# lihini_pcb_2021-05-16.net
KiCad netlist of a schematic drawn in EasyEDA
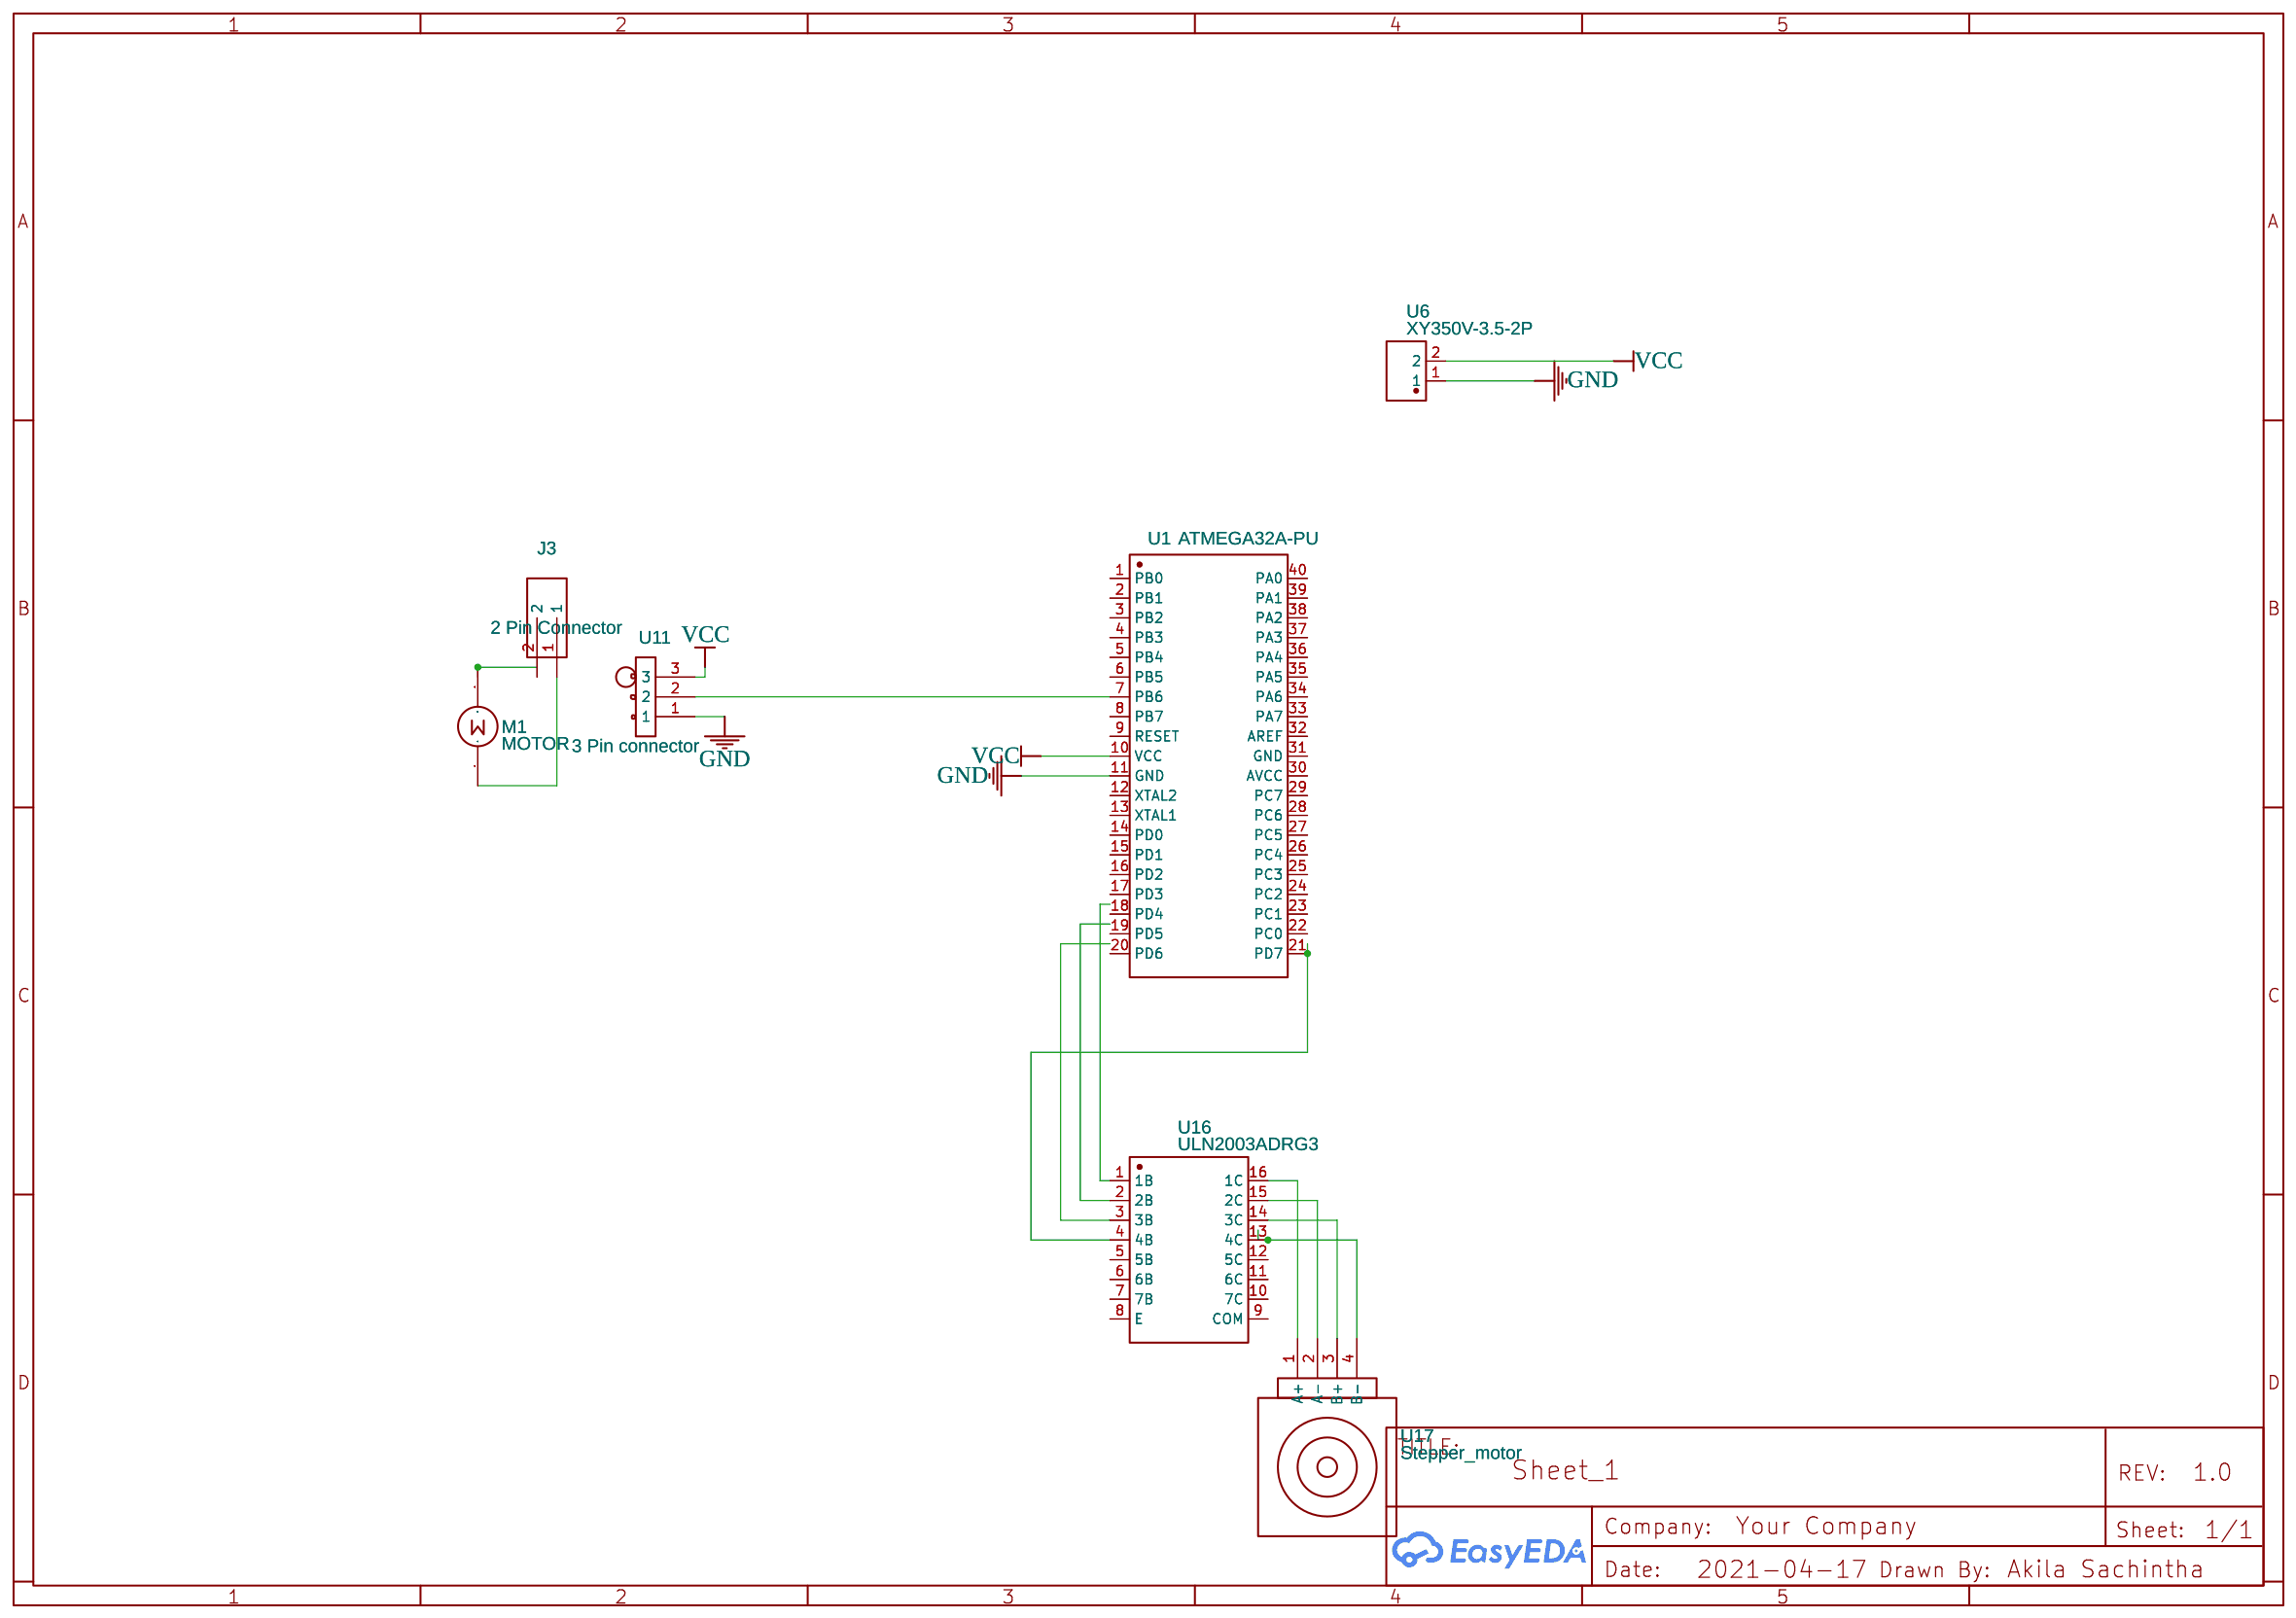
[diagram p0: schematic sheet]

(export (version "E")
  (design (tool "Eeschema 10.0.6"))
  (components
    (comp (ref "J3") (value "2 Pin Connector") (libsource (lib "") (part "2 Pin Connector")))
    (comp (ref "M1") (value "MOTOR") (libsource (lib "") (part "MOTOR")))
    (comp (ref "U1")
      (value "ATMEGA32A-PU")
      (fields (field (name "BOM_Supplier Part") "C12703"))
      (libsource (lib "") (part "ATMEGA32A-PU"))
    )
    (comp (ref "U6")
      (value "XY350V-3.5-2P")
      (fields (field (name "BOM_Supplier Part") "C784942"))
      (libsource (lib "") (part "XY350V-3.5-2P"))
    )
    (comp (ref "U11")
      (value "3 Pin connector")
      (fields (field (name "BOM_Manufacturer Part") "pin 3"))
      (libsource (lib "") (part "3 Pin connector"))
    )
    (comp (ref "U16") (value "ULN2003ADRG3") (libsource (lib "") (part "ULN2003ADRG3")))
    (comp (ref "U17")
      (value "Stepper_motor")
      (fields (field (name "BOM_Manufacturer Part") "NEMA 23 Stepper Motor"))
      (libsource (lib "") (part "Stepper_motor"))
    )
  )
  (nets
    (net (code "1") (name "GND") (class "Default")
      (node (ref "U1") (pin "11") (pinfunction "GND_11") (pintype "unspecified"))
      (node (ref "U11") (pin "1") (pinfunction "1_1") (pintype "unspecified"))
      (node (ref "U6") (pin "1") (pinfunction "1_1") (pintype "unspecified"))
    )
    (net (code "2") (name "Net-(J3-Pad1)") (class "Default")
      (node (ref "J3") (pin "1") (pinfunction "1_1") (pintype "unspecified"))
      (node (ref "M1") (pin "1") (pinfunction "1_1") (pintype "unspecified"))
    )
    (net (code "3") (name "Net-(U1-PB6)") (class "Default")
      (node (ref "U1") (pin "7") (pinfunction "PB6_7") (pintype "unspecified"))
      (node (ref "U11") (pin "2") (pinfunction "2_2") (pintype "unspecified"))
    )
    (net (code "4") (name "Net-(U1-PD7)") (class "Default")
      (node (ref "U1") (pin "21") (pinfunction "PD7_21") (pintype "unspecified"))
      (node (ref "U16") (pin "4") (pinfunction "4B_4") (pintype "unspecified"))
    )
    (net (code "5") (name "Net-(U16-1C)") (class "Default")
      (node (ref "U16") (pin "16") (pinfunction "1C_16") (pintype "unspecified"))
      (node (ref "U17") (pin "1") (pinfunction "A+_1") (pintype "unspecified"))
    )
    (net (code "6") (name "Net-(U16-2C)") (class "Default")
      (node (ref "U16") (pin "15") (pinfunction "2C_15") (pintype "unspecified"))
      (node (ref "U17") (pin "2") (pinfunction "A-_2") (pintype "unspecified"))
    )
    (net (code "7") (name "Net-(U16-3C)") (class "Default")
      (node (ref "U16") (pin "14") (pinfunction "3C_14") (pintype "unspecified"))
      (node (ref "U17") (pin "3") (pinfunction "B+_3") (pintype "unspecified"))
    )
    (net (code "8") (name "Net-(U16-4C)") (class "Default")
      (node (ref "U16") (pin "13") (pinfunction "4C_13") (pintype "unspecified"))
      (node (ref "U17") (pin "4") (pinfunction "B-_4") (pintype "unspecified"))
    )
    (net (code "9") (name "VCC") (class "Default")
      (node (ref "U1") (pin "10") (pinfunction "VCC_10") (pintype "unspecified"))
      (node (ref "U11") (pin "3") (pinfunction "3_3") (pintype "unspecified"))
      (node (ref "U6") (pin "2") (pinfunction "2_2") (pintype "unspecified"))
    )
    (net (code "10") (name "unconnected-(J3-Pad2)") (class "Default")
      (node (ref "J3") (pin "2") (pinfunction "2_2") (pintype "unspecified"))
    )
    (net (code "11") (name "unconnected-(M1-Pad2)") (class "Default")
      (node (ref "M1") (pin "2") (pinfunction "2_2") (pintype "unspecified"))
    )
    (net (code "12") (name "unconnected-(U1-AREF-Pad32)") (class "Default")
      (node (ref "U1") (pin "32") (pinfunction "AREF_32") (pintype "unspecified"))
    )
    (net (code "13") (name "unconnected-(U1-AVCC-Pad30)") (class "Default")
      (node (ref "U1") (pin "30") (pinfunction "AVCC_30") (pintype "unspecified"))
    )
    (net (code "14") (name "unconnected-(U1-GND-Pad31)") (class "Default")
      (node (ref "U1") (pin "31") (pinfunction "GND_31") (pintype "unspecified"))
    )
    (net (code "15") (name "unconnected-(U1-PA0-Pad40)") (class "Default")
      (node (ref "U1") (pin "40") (pinfunction "PA0_40") (pintype "unspecified"))
    )
    (net (code "16") (name "unconnected-(U1-PA1-Pad39)") (class "Default")
      (node (ref "U1") (pin "39") (pinfunction "PA1_39") (pintype "unspecified"))
    )
    (net (code "17") (name "unconnected-(U1-PA2-Pad38)") (class "Default")
      (node (ref "U1") (pin "38") (pinfunction "PA2_38") (pintype "unspecified"))
    )
    (net (code "18") (name "unconnected-(U1-PA3-Pad37)") (class "Default")
      (node (ref "U1") (pin "37") (pinfunction "PA3_37") (pintype "unspecified"))
    )
    (net (code "19") (name "unconnected-(U1-PA4-Pad36)") (class "Default")
      (node (ref "U1") (pin "36") (pinfunction "PA4_36") (pintype "unspecified"))
    )
    (net (code "20") (name "unconnected-(U1-PA5-Pad35)") (class "Default")
      (node (ref "U1") (pin "35") (pinfunction "PA5_35") (pintype "unspecified"))
    )
    (net (code "21") (name "unconnected-(U1-PA6-Pad34)") (class "Default")
      (node (ref "U1") (pin "34") (pinfunction "PA6_34") (pintype "unspecified"))
    )
    (net (code "22") (name "unconnected-(U1-PA7-Pad33)") (class "Default")
      (node (ref "U1") (pin "33") (pinfunction "PA7_33") (pintype "unspecified"))
    )
    (net (code "23") (name "unconnected-(U1-PB0-Pad1)") (class "Default")
      (node (ref "U1") (pin "1") (pinfunction "PB0_1") (pintype "unspecified"))
    )
    (net (code "24") (name "unconnected-(U1-PB1-Pad2)") (class "Default")
      (node (ref "U1") (pin "2") (pinfunction "PB1_2") (pintype "unspecified"))
    )
    (net (code "25") (name "unconnected-(U1-PB2-Pad3)") (class "Default")
      (node (ref "U1") (pin "3") (pinfunction "PB2_3") (pintype "unspecified"))
    )
    (net (code "26") (name "unconnected-(U1-PB3-Pad4)") (class "Default")
      (node (ref "U1") (pin "4") (pinfunction "PB3_4") (pintype "unspecified"))
    )
    (net (code "27") (name "unconnected-(U1-PB4-Pad5)") (class "Default")
      (node (ref "U1") (pin "5") (pinfunction "PB4_5") (pintype "unspecified"))
    )
    (net (code "28") (name "unconnected-(U1-PB5-Pad6)") (class "Default")
      (node (ref "U1") (pin "6") (pinfunction "PB5_6") (pintype "unspecified"))
    )
    (net (code "29") (name "unconnected-(U1-PB7-Pad8)") (class "Default")
      (node (ref "U1") (pin "8") (pinfunction "PB7_8") (pintype "unspecified"))
    )
    (net (code "30") (name "unconnected-(U1-PC0-Pad22)") (class "Default")
      (node (ref "U1") (pin "22") (pinfunction "PC0_22") (pintype "unspecified"))
    )
    (net (code "31") (name "unconnected-(U1-PC1-Pad23)") (class "Default")
      (node (ref "U1") (pin "23") (pinfunction "PC1_23") (pintype "unspecified"))
    )
    (net (code "32") (name "unconnected-(U1-PC2-Pad24)") (class "Default")
      (node (ref "U1") (pin "24") (pinfunction "PC2_24") (pintype "unspecified"))
    )
    (net (code "33") (name "unconnected-(U1-PC3-Pad25)") (class "Default")
      (node (ref "U1") (pin "25") (pinfunction "PC3_25") (pintype "unspecified"))
    )
    (net (code "34") (name "unconnected-(U1-PC4-Pad26)") (class "Default")
      (node (ref "U1") (pin "26") (pinfunction "PC4_26") (pintype "unspecified"))
    )
    (net (code "35") (name "unconnected-(U1-PC5-Pad27)") (class "Default")
      (node (ref "U1") (pin "27") (pinfunction "PC5_27") (pintype "unspecified"))
    )
    (net (code "36") (name "unconnected-(U1-PC6-Pad28)") (class "Default")
      (node (ref "U1") (pin "28") (pinfunction "PC6_28") (pintype "unspecified"))
    )
    (net (code "37") (name "unconnected-(U1-PC7-Pad29)") (class "Default")
      (node (ref "U1") (pin "29") (pinfunction "PC7_29") (pintype "unspecified"))
    )
    (net (code "38") (name "unconnected-(U1-PD0-Pad14)") (class "Default")
      (node (ref "U1") (pin "14") (pinfunction "PD0_14") (pintype "unspecified"))
    )
    (net (code "39") (name "unconnected-(U1-PD1-Pad15)") (class "Default")
      (node (ref "U1") (pin "15") (pinfunction "PD1_15") (pintype "unspecified"))
    )
    (net (code "40") (name "unconnected-(U1-PD2-Pad16)") (class "Default")
      (node (ref "U1") (pin "16") (pinfunction "PD2_16") (pintype "unspecified"))
    )
    (net (code "41") (name "unconnected-(U1-PD3-Pad17)") (class "Default")
      (node (ref "U1") (pin "17") (pinfunction "PD3_17") (pintype "unspecified"))
    )
    (net (code "42") (name "unconnected-(U1-PD4-Pad18)") (class "Default")
      (node (ref "U1") (pin "18") (pinfunction "PD4_18") (pintype "unspecified"))
    )
    (net (code "43") (name "unconnected-(U1-PD5-Pad19)") (class "Default")
      (node (ref "U1") (pin "19") (pinfunction "PD5_19") (pintype "unspecified"))
    )
    (net (code "44") (name "unconnected-(U1-PD6-Pad20)") (class "Default")
      (node (ref "U1") (pin "20") (pinfunction "PD6_20") (pintype "unspecified"))
    )
    (net (code "45") (name "unconnected-(U1-RESET-Pad9)") (class "Default")
      (node (ref "U1") (pin "9") (pinfunction "RESET_9") (pintype "unspecified"))
    )
    (net (code "46") (name "unconnected-(U1-XTAL1-Pad13)") (class "Default")
      (node (ref "U1") (pin "13") (pinfunction "XTAL1_13") (pintype "unspecified"))
    )
    (net (code "47") (name "unconnected-(U1-XTAL2-Pad12)") (class "Default")
      (node (ref "U1") (pin "12") (pinfunction "XTAL2_12") (pintype "unspecified"))
    )
    (net (code "48") (name "unconnected-(U16-1B-Pad1)") (class "Default")
      (node (ref "U16") (pin "1") (pinfunction "1B_1") (pintype "unspecified"))
    )
    (net (code "49") (name "unconnected-(U16-2B-Pad2)") (class "Default")
      (node (ref "U16") (pin "2") (pinfunction "2B_2") (pintype "unspecified"))
    )
    (net (code "50") (name "unconnected-(U16-3B-Pad3)") (class "Default")
      (node (ref "U16") (pin "3") (pinfunction "3B_3") (pintype "unspecified"))
    )
    (net (code "51") (name "unconnected-(U16-5B-Pad5)") (class "Default")
      (node (ref "U16") (pin "5") (pinfunction "5B_5") (pintype "unspecified"))
    )
    (net (code "52") (name "unconnected-(U16-5C-Pad12)") (class "Default")
      (node (ref "U16") (pin "12") (pinfunction "5C_12") (pintype "unspecified"))
    )
    (net (code "53") (name "unconnected-(U16-6B-Pad6)") (class "Default")
      (node (ref "U16") (pin "6") (pinfunction "6B_6") (pintype "unspecified"))
    )
    (net (code "54") (name "unconnected-(U16-6C-Pad11)") (class "Default")
      (node (ref "U16") (pin "11") (pinfunction "6C_11") (pintype "unspecified"))
    )
    (net (code "55") (name "unconnected-(U16-7B-Pad7)") (class "Default")
      (node (ref "U16") (pin "7") (pinfunction "7B_7") (pintype "unspecified"))
    )
    (net (code "56") (name "unconnected-(U16-7C-Pad10)") (class "Default")
      (node (ref "U16") (pin "10") (pinfunction "7C_10") (pintype "unspecified"))
    )
    (net (code "57") (name "unconnected-(U16-COM-Pad9)") (class "Default")
      (node (ref "U16") (pin "9") (pinfunction "COM_9") (pintype "unspecified"))
    )
    (net (code "58") (name "unconnected-(U16-E-Pad8)") (class "Default")
      (node (ref "U16") (pin "8") (pinfunction "E_8") (pintype "unspecified"))
    )
  )
)
